# Sheet1.net
KiCad netlist of a schematic drawn in Altium Designer
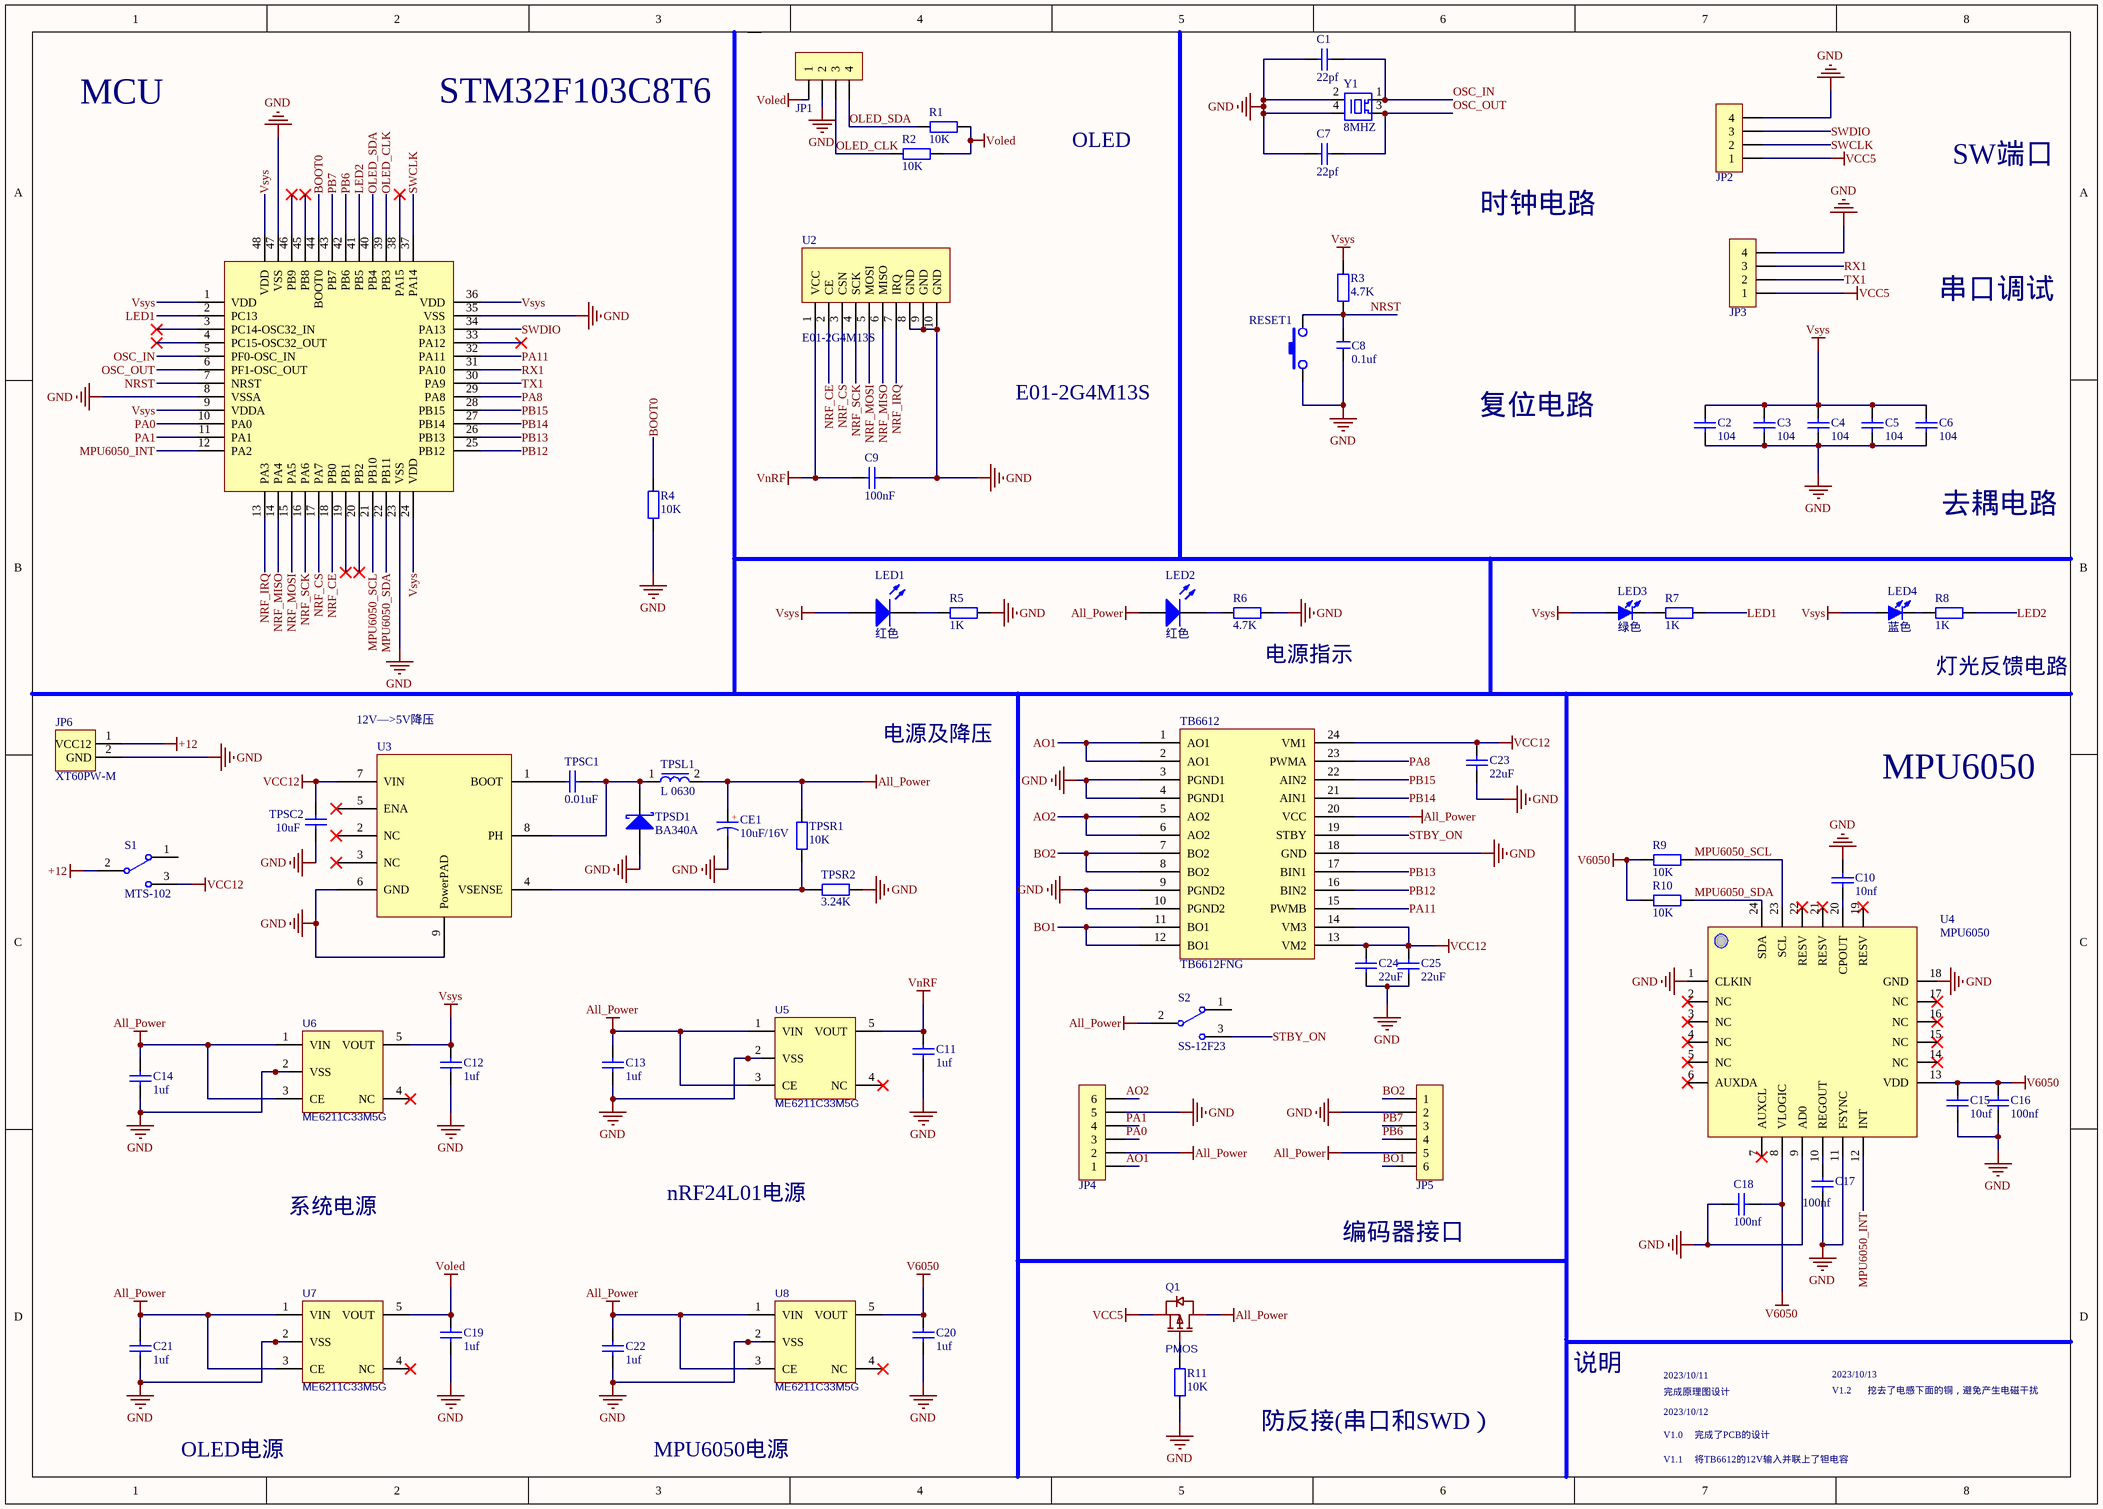
[diagram p0: Sheet1.SchDoc]

(export (version "E")
  (design (tool "Eeschema 10.0.6"))
  (components
    (comp (ref "C1")
      (value "22pf")
      (footprint "C0603_M")
      (description "贴片电容")
      (libsource (lib "cdud开发板") (part "C"))
    )
    (comp (ref "C2")
      (value "104")
      (footprint "C0603_M")
      (description "贴片电容/MLCC电容")
      (libsource (lib "0.1 - 电阻-电容-电感-保险丝-晶振-晶体-磁珠-电位器-法拉电容-馈通电容") (part "C"))
    )
    (comp (ref "C3")
      (value "104")
      (footprint "C0603_M")
      (description "贴片电容/MLCC电容")
      (libsource (lib "0.1 - 电阻-电容-电感-保险丝-晶振-晶体-磁珠-电位器-法拉电容-馈通电容") (part "C"))
    )
    (comp (ref "C4")
      (value "104")
      (footprint "C0603_M")
      (description "贴片电容/MLCC电容")
      (libsource (lib "0.1 - 电阻-电容-电感-保险丝-晶振-晶体-磁珠-电位器-法拉电容-馈通电容") (part "C"))
    )
    (comp (ref "C5")
      (value "104")
      (footprint "C0603_M")
      (description "贴片电容/MLCC电容")
      (libsource (lib "0.1 - 电阻-电容-电感-保险丝-晶振-晶体-磁珠-电位器-法拉电容-馈通电容") (part "C"))
    )
    (comp (ref "C6")
      (value "104")
      (footprint "C0603_M")
      (description "贴片电容/MLCC电容")
      (libsource (lib "0.1 - 电阻-电容-电感-保险丝-晶振-晶体-磁珠-电位器-法拉电容-馈通电容") (part "C"))
    )
    (comp (ref "C7")
      (value "22pf")
      (footprint "C0603_M")
      (description "贴片电容")
      (libsource (lib "cdud开发板") (part "C"))
    )
    (comp (ref "C8")
      (value "0.1uf")
      (footprint "C0603_M")
      (description "无极性贴片电容")
      (fields (field (name "版权归属") "源创客"))
      (libsource (lib "AllSystem") (part "C"))
    )
    (comp (ref "C9")
      (value "100nF")
      (footprint "C0603_M")
      (description "贴片电容")
      (libsource (lib "数传模块") (part "C"))
    )
    (comp (ref "C10")
      (value "10nf")
      (footprint "C0603_M")
      (description "贴片电容")
      (libsource (lib "cdud开发板") (part "C_1"))
    )
    (comp (ref "C11")
      (value "1uf")
      (footprint "C0603_M")
      (description "贴片电容")
      (libsource (lib "cdud开发板") (part "C_3"))
    )
    (comp (ref "C12")
      (value "1uf")
      (footprint "C0603_M")
      (description "贴片电容")
      (libsource (lib "cdud开发板") (part "C_3"))
    )
    (comp (ref "C13")
      (value "1uf")
      (footprint "C0603_M")
      (description "贴片电容")
      (libsource (lib "cdud开发板") (part "C_3"))
    )
    (comp (ref "C14")
      (value "1uf")
      (footprint "C0603_M")
      (description "贴片电容")
      (libsource (lib "cdud开发板") (part "C_3"))
    )
    (comp (ref "C15")
      (value "10uf")
      (footprint "C0603_M")
      (description "贴片电容")
      (libsource (lib "cdud开发板") (part "C_1"))
    )
    (comp (ref "C16")
      (value "100nf")
      (footprint "C0603_M")
      (description "贴片电容")
      (libsource (lib "cdud开发板") (part "C_1"))
    )
    (comp (ref "C17")
      (value "100nf")
      (footprint "C0603_M")
      (description "贴片电容")
      (libsource (lib "cdud开发板") (part "C_1"))
    )
    (comp (ref "C18")
      (value "100nf")
      (footprint "C0603_M")
      (description "贴片电容")
      (libsource (lib "cdud开发板") (part "C_1"))
    )
    (comp (ref "C19")
      (value "1uf")
      (footprint "C0603_M")
      (description "贴片电容")
      (libsource (lib "cdud开发板") (part "C_3"))
    )
    (comp (ref "C20")
      (value "1uf")
      (footprint "C0603_M")
      (description "贴片电容")
      (libsource (lib "cdud开发板") (part "C_3"))
    )
    (comp (ref "C21")
      (value "1uf")
      (footprint "C0603_M")
      (description "贴片电容")
      (libsource (lib "cdud开发板") (part "C_3"))
    )
    (comp (ref "C22")
      (value "1uf")
      (footprint "C0603_M")
      (description "贴片电容")
      (libsource (lib "cdud开发板") (part "C_3"))
    )
    (comp (ref "C23")
      (value "22uF")
      (footprint "C_3216")
      (description "贴片电容/MLCC电容")
      (libsource (lib "0.1 - 电阻-电容-电感-保险丝-晶振-晶体-磁珠-电位器-法拉电容-馈通电容") (part "C"))
    )
    (comp (ref "C24")
      (value "22uF")
      (footprint "C0603_M")
      (description "贴片电容/MLCC电容")
      (libsource (lib "0.1 - 电阻-电容-电感-保险丝-晶振-晶体-磁珠-电位器-法拉电容-馈通电容") (part "C"))
    )
    (comp (ref "C25")
      (value "22uF")
      (footprint "C0603_M")
      (description "贴片电容/MLCC电容")
      (libsource (lib "0.1 - 电阻-电容-电感-保险丝-晶振-晶体-磁珠-电位器-法拉电容-馈通电容") (part "C"))
    )
    (comp (ref "CE1")
      (value "10uF/16V")
      (footprint "CE-3.5*8*11.5 - BK - duplicate")
      (description "直插电解电容")
      (libsource (lib "0.1 - 电阻-电容-电感-晶振-晶体-磁珠-电位器") (part "CE"))
    )
    (comp (ref "JP1")
      (value "HDR-1X4")
      (footprint "HDR2.54-M-LI-4P")
      (description "4P接插件")
      (libsource (lib "5.5 - 2.54mm(100mil)连接器(XH2.54)") (part "Header 4"))
    )
    (comp (ref "JP2")
      (value "HDR-1X4")
      (footprint "HDR2.54-M-LI-4P")
      (description "4P接插件")
      (libsource (lib "") (part "Header 4_1"))
    )
    (comp (ref "JP3")
      (value "HDR-1X4")
      (footprint "HDR2.54-M-LI-4P")
      (description "4P接插件")
      (libsource (lib "") (part "Header 4_1"))
    )
    (comp (ref "JP4")
      (value "HDR-1X6")
      (footprint "XH2.54-LI-6P")
      (description "6P接插件")
      (libsource (lib "5.5 - 2.54mm连接器(KF2EDGK_XH2.54_2.54排针排母)") (part "Header 6"))
    )
    (comp (ref "JP5")
      (value "HDR-1X6")
      (footprint "XH2.54-LI-6P")
      (description "6P接插件")
      (libsource (lib "") (part "Header 6_1"))
    )
    (comp (ref "JP6")
      (value "XT60PW-M")
      (footprint "XT60PW-M")
      (description "XT60PW-M弯插")
      (libsource (lib "XT60PW") (part "XT60PW"))
    )
    (comp (ref "LED1")
      (value "红色")
      (footprint "LED0805_B")
      (description "贴片LED")
      (libsource (lib "0.3 - LED发光二极管-IR二极管_接收管-光耦") (part "LED"))
    )
    (comp (ref "LED2")
      (value "红色")
      (footprint "LED0805_B")
      (description "贴片LED")
      (libsource (lib "0.3 - LED发光二极管-IR二极管_接收管-光耦") (part "LED"))
    )
    (comp (ref "LED3")
      (value "绿色")
      (footprint "LED0805_B")
      (description "贴片LED")
      (libsource (lib "0.3 - LED发光二极管-IR二极管_接收管-光耦") (part "LED-SMD"))
    )
    (comp (ref "LED4")
      (value "蓝色")
      (footprint "LED0805_R")
      (description "贴片LED")
      (libsource (lib "0.3 - LED发光二极管-IR二极管_接收管-光耦") (part "LED-SMD"))
    )
    (comp (ref "MCU")
      (value "STM32F103C8T6")
      (footprint "STM-LQFP48_N")
      (libsource (lib "Schlib1") (part "STM32_LQFP48"))
    )
    (comp (ref "Q1")
      (value "PMOS")
      (footprint "SOT23")
      (fields
        (field (name "BOM_SUPPLIER PART") "C727156")
        (field (name "BOM_MANUFACTURER PART") "AO3401")
        (field (name "CONTRIBUTOR") "LCSC")
      )
      (libsource (lib "IMU") (part "PMOS"))
    )
    (comp (ref "R1")
      (value "10K")
      (footprint "R0603_M")
      (description "贴片电阻")
      (libsource (lib "cdud开发板") (part "R_1"))
    )
    (comp (ref "R2")
      (value "10K")
      (footprint "R0603_M")
      (description "贴片电阻")
      (libsource (lib "cdud开发板") (part "R_1"))
    )
    (comp (ref "R3")
      (value "4.7K")
      (footprint "R0603_M")
      (description "贴片电阻")
      (fields (field (name "版权归属") "源创客"))
      (libsource (lib "AllSystem") (part "R"))
    )
    (comp (ref "R4")
      (value "10K")
      (footprint "R0603_M")
      (description "贴片电阻")
      (libsource (lib "cdud开发板") (part "R"))
    )
    (comp (ref "R5")
      (value "1K")
      (footprint "R0603_M")
      (description "贴片电阻")
      (libsource (lib "0.1 - 电阻-电容-电感-晶振-晶体-磁珠-电位器") (part "R"))
    )
    (comp (ref "R6")
      (value "4.7K")
      (footprint "R0603_M")
      (description "贴片电阻")
      (libsource (lib "cdud开发板") (part "R"))
    )
    (comp (ref "R7")
      (value "1K")
      (footprint "R0603_M")
      (description "贴片电阻")
      (libsource (lib "0.1 - 电阻-电容-电感-晶振-晶体-磁珠-电位器") (part "R"))
    )
    (comp (ref "R8")
      (value "1K")
      (footprint "R0603_M")
      (description "贴片电阻")
      (libsource (lib "0.1 - 电阻-电容-电感-晶振-晶体-磁珠-电位器") (part "R"))
    )
    (comp (ref "R9")
      (value "10K")
      (footprint "R0603_M")
      (description "贴片电阻")
      (libsource (lib "cdud开发板") (part "R"))
    )
    (comp (ref "R10")
      (value "10K")
      (footprint "R0603_M")
      (description "贴片电阻")
      (libsource (lib "cdud开发板") (part "R"))
    )
    (comp (ref "R11")
      (value "10K")
      (footprint "R0603_M")
      (description "贴片电阻")
      (libsource (lib "数传模块") (part "R"))
    )
    (comp (ref "RESET1") (value "KEY") (footprint "SW SMD-3*6*5") (libsource (lib "STM32") (part "KEY")))
    (comp (ref "S1")
      (value "MTS-102")
      (footprint "MTS-10x")
      (description "MTS10x系列3脚扭子开关")
      (fields (field (name "版权归属") "源创客"))
      (libsource (lib "S109Controller") (part "MTS-10x"))
    )
    (comp (ref "S2")
      (value "SS-12F23")
      (footprint "SS-12D0703")
      (description "1路波动开关")
      (fields (field (name "版权归属") "源创客"))
      (libsource (lib "Remote_control") (part "SSW-1P"))
    )
    (comp (ref "TB6612")
      (value "TB6612FNG")
      (footprint "SSOP-24_L8.3-W5.6-P0.65-LS7.6-BL")
      (libsource (lib "Schlib1") (part "TB6612FNG"))
    )
    (comp (ref "TPSC1")
      (value "0.01uF")
      (footprint "C0603_M")
      (description "贴片电容")
      (libsource (lib "0.1 - 电阻-电容-电感-晶振-晶体-磁珠-电位器") (part "C"))
    )
    (comp (ref "TPSC2")
      (value "10uF")
      (footprint "C0603_M")
      (description "贴片电容")
      (libsource (lib "0.1 - 电阻-电容-电感-晶振-晶体-磁珠-电位器") (part "C"))
    )
    (comp (ref "TPSD1")
      (value "BA340A")
      (footprint "SMA")
      (description "肖特基二极管")
      (libsource (lib "0.2 - 二极管-TVS-ESD-整流桥") (part "SS210"))
    )
    (comp (ref "TPSL1")
      (value "L 0630")
      (footprint "L 0630")
      (description "SMA")
      (libsource (lib "mylibrary") (part "L 0630"))
    )
    (comp (ref "TPSR1")
      (value "10K")
      (footprint "R0603_M")
      (description "贴片电阻")
      (libsource (lib "0.1 - 电阻-电容-电感-晶振-晶体-磁珠-电位器") (part "R"))
    )
    (comp (ref "TPSR2")
      (value "3.24K")
      (footprint "R0603_M")
      (description "贴片电阻")
      (libsource (lib "0.1 - 电阻-电容-电感-晶振-晶体-磁珠-电位器") (part "R"))
    )
    (comp (ref "U2")
      (value "E01-2G4M13S")
      (footprint "E01-2G4M01S1B")
      (description "贴片NREF24L01")
      (libsource (lib "IMU") (part "E01-2G4M13S"))
    )
    (comp (ref "U3")
      (value "TPS5430DDAR")
      (footprint "TPS5430DAR")
      (description "输出额定电流3A 纹波30mV")
      (libsource (lib "mylibrary") (part "TPS5430DDAR"))
    )
    (comp (ref "U4")
      (value "MPU6050")
      (footprint "QFN24 4x4_M")
      (description "9轴运动处理传感器")
      (libsource (lib "S109Controller") (part "MPU6050"))
    )
    (comp (ref "U5")
      (value "ME6211C33M5G")
      (footprint "SOT-23-5")
      (description "LDO 3.3V/0.5A")
      (libsource (lib "0.7 - 电源类芯片") (part "ME6211C33"))
    )
    (comp (ref "U6")
      (value "ME6211C33M5G")
      (footprint "SOT-23-5")
      (description "LDO 3.3V/0.5A")
      (libsource (lib "0.7 - 电源类芯片") (part "ME6211C33"))
    )
    (comp (ref "U7")
      (value "ME6211C33M5G")
      (footprint "SOT-23-5")
      (description "LDO 3.3V/0.5A")
      (libsource (lib "0.7 - 电源类芯片") (part "ME6211C33"))
    )
    (comp (ref "U8")
      (value "ME6211C33M5G")
      (footprint "SOT-23-5")
      (description "LDO 3.3V/0.5A")
      (libsource (lib "0.7 - 电源类芯片") (part "ME6211C33"))
    )
    (comp (ref "Y1") (value "8MHZ") (footprint "3225") (libsource (lib "cdud开发板") (part "jinzheng")))
  )
  (nets
    (net (code "1") (name "+12") (class "Default")
      (node (ref "JP6") (pin "1") (pinfunction "VCC12_1") (pintype "passive"))
      (node (ref "S1") (pin "2") (pinfunction "2_2") (pintype "passive"))
    )
    (net (code "2") (name "/AO1") (class "Default")
      (node (ref "JP4") (pin "1") (pinfunction "1_1") (pintype "passive"))
      (node (ref "TB6612") (pin "1") (pinfunction "AO1_1") (pintype "passive"))
      (node (ref "TB6612") (pin "2") (pinfunction "AO1_2") (pintype "passive"))
    )
    (net (code "3") (name "/AO2") (class "Default")
      (node (ref "JP4") (pin "6") (pinfunction "6_6") (pintype "passive"))
      (node (ref "TB6612") (pin "5") (pinfunction "AO2_5") (pintype "passive"))
      (node (ref "TB6612") (pin "6") (pinfunction "AO2_6") (pintype "passive"))
    )
    (net (code "4") (name "/BO1") (class "Default")
      (node (ref "JP5") (pin "6") (pinfunction "6_6") (pintype "passive"))
      (node (ref "TB6612") (pin "11") (pinfunction "BO1_11") (pintype "passive"))
      (node (ref "TB6612") (pin "12") (pinfunction "BO1_12") (pintype "passive"))
    )
    (net (code "5") (name "/BO2") (class "Default")
      (node (ref "JP5") (pin "1") (pinfunction "1_1") (pintype "passive"))
      (node (ref "TB6612") (pin "7") (pinfunction "BO2_7") (pintype "passive"))
      (node (ref "TB6612") (pin "8") (pinfunction "BO2_8") (pintype "passive"))
    )
    (net (code "6") (name "/BOOT0") (class "Default")
      (node (ref "MCU") (pin "44") (pinfunction "BOOT0_44") (pintype "passive"))
      (node (ref "R4") (pin "1") (pinfunction "1_1") (pintype "passive"))
    )
    (net (code "7") (name "/LED1") (class "Default")
      (node (ref "MCU") (pin "2") (pinfunction "PC13_2") (pintype "passive"))
      (node (ref "R7") (pin "2") (pinfunction "2_2") (pintype "passive"))
    )
    (net (code "8") (name "/LED2") (class "Default")
      (node (ref "MCU") (pin "41") (pinfunction "PB5_41") (pintype "passive"))
      (node (ref "R8") (pin "2") (pinfunction "2_2") (pintype "passive"))
    )
    (net (code "9") (name "/MPU6050_INT") (class "Default")
      (node (ref "MCU") (pin "12") (pinfunction "PA2_12") (pintype "passive"))
      (node (ref "U4") (pin "12") (pinfunction "INT_12") (pintype "passive"))
    )
    (net (code "10") (name "/MPU6050_SCL") (class "Default")
      (node (ref "MCU") (pin "21") (pinfunction "PB10_21") (pintype "passive"))
      (node (ref "R9") (pin "2") (pinfunction "2_2") (pintype "passive"))
      (node (ref "U4") (pin "23") (pinfunction "SCL_23") (pintype "passive"))
    )
    (net (code "11") (name "/MPU6050_SDA") (class "Default")
      (node (ref "MCU") (pin "22") (pinfunction "PB11_22") (pintype "passive"))
      (node (ref "R10") (pin "2") (pinfunction "2_2") (pintype "passive"))
      (node (ref "U4") (pin "24") (pinfunction "SDA_24") (pintype "passive"))
    )
    (net (code "12") (name "/NRF_CE") (class "Default")
      (node (ref "MCU") (pin "18") (pinfunction "PB0_18") (pintype "passive"))
      (node (ref "U2") (pin "2") (pinfunction "CE_2") (pintype "passive"))
    )
    (net (code "13") (name "/NRF_CS") (class "Default")
      (node (ref "MCU") (pin "17") (pinfunction "PA7_17") (pintype "passive"))
      (node (ref "U2") (pin "3") (pinfunction "CSN_3") (pintype "passive"))
    )
    (net (code "14") (name "/NRF_IRQ") (class "Default")
      (node (ref "MCU") (pin "13") (pinfunction "PA3_13") (pintype "passive"))
      (node (ref "U2") (pin "7") (pinfunction "IRQ_7") (pintype "passive"))
    )
    (net (code "15") (name "/NRF_MISO") (class "Default")
      (node (ref "MCU") (pin "14") (pinfunction "PA4_14") (pintype "passive"))
      (node (ref "U2") (pin "6") (pinfunction "MISO_6") (pintype "passive"))
    )
    (net (code "16") (name "/NRF_MOSI") (class "Default")
      (node (ref "MCU") (pin "15") (pinfunction "PA5_15") (pintype "passive"))
      (node (ref "U2") (pin "5") (pinfunction "MOSI_5") (pintype "passive"))
    )
    (net (code "17") (name "/NRF_SCK") (class "Default")
      (node (ref "MCU") (pin "16") (pinfunction "PA6_16") (pintype "passive"))
      (node (ref "U2") (pin "4") (pinfunction "SCK_4") (pintype "passive"))
    )
    (net (code "18") (name "/NRST") (class "Default")
      (node (ref "C8") (pin "1") (pinfunction "1_1") (pintype "passive"))
      (node (ref "MCU") (pin "7") (pinfunction "NRST_7") (pintype "passive"))
      (node (ref "R3") (pin "1") (pinfunction "1_1") (pintype "passive"))
      (node (ref "RESET1") (pin "2") (pinfunction "2_2") (pintype "passive"))
    )
    (net (code "19") (name "/OLED_CLK") (class "Default")
      (node (ref "JP1") (pin "3") (pinfunction "3_3") (pintype "passive"))
      (node (ref "MCU") (pin "39") (pinfunction "PB3_39") (pintype "passive"))
      (node (ref "R2") (pin "1") (pinfunction "1_1") (pintype "passive"))
    )
    (net (code "20") (name "/OLED_SDA") (class "Default")
      (node (ref "JP1") (pin "4") (pinfunction "4_4") (pintype "passive"))
      (node (ref "MCU") (pin "40") (pinfunction "PB4_40") (pintype "passive"))
      (node (ref "R1") (pin "1") (pinfunction "1_1") (pintype "passive"))
    )
    (net (code "21") (name "/OSC_IN") (class "Default")
      (node (ref "C1") (pin "2") (pinfunction "2_2") (pintype "passive"))
      (node (ref "MCU") (pin "5") (pinfunction "PF0-OSC_IN_5") (pintype "passive"))
      (node (ref "Y1") (pin "1") (pinfunction "XTAL1_1") (pintype "passive"))
    )
    (net (code "22") (name "/OSC_OUT") (class "Default")
      (node (ref "C7") (pin "2") (pinfunction "2_2") (pintype "passive"))
      (node (ref "MCU") (pin "6") (pinfunction "PF1-OSC_OUT_6") (pintype "passive"))
      (node (ref "Y1") (pin "3") (pinfunction "XTAL3_3") (pintype "passive"))
    )
    (net (code "23") (name "/PA0") (class "Default")
      (node (ref "JP4") (pin "3") (pinfunction "3_3") (pintype "passive"))
      (node (ref "MCU") (pin "10") (pinfunction "PA0_10") (pintype "passive"))
    )
    (net (code "24") (name "/PA1") (class "Default")
      (node (ref "JP4") (pin "4") (pinfunction "4_4") (pintype "passive"))
      (node (ref "MCU") (pin "11") (pinfunction "PA1_11") (pintype "passive"))
    )
    (net (code "25") (name "/PA8") (class "Default")
      (node (ref "MCU") (pin "29") (pinfunction "PA8_29") (pintype "passive"))
      (node (ref "TB6612") (pin "23") (pinfunction "PWMA_23") (pintype "passive"))
    )
    (net (code "26") (name "/PA11") (class "Default")
      (node (ref "MCU") (pin "32") (pinfunction "PA11_32") (pintype "passive"))
      (node (ref "TB6612") (pin "15") (pinfunction "PWMB_15") (pintype "passive"))
    )
    (net (code "27") (name "/PB6") (class "Default")
      (node (ref "JP5") (pin "4") (pinfunction "4_4") (pintype "passive"))
      (node (ref "MCU") (pin "42") (pinfunction "PB6_42") (pintype "passive"))
    )
    (net (code "28") (name "/PB7") (class "Default")
      (node (ref "JP5") (pin "3") (pinfunction "3_3") (pintype "passive"))
      (node (ref "MCU") (pin "43") (pinfunction "PB7_43") (pintype "passive"))
    )
    (net (code "29") (name "/PB12") (class "Default")
      (node (ref "MCU") (pin "25") (pinfunction "PB12_25") (pintype "passive"))
      (node (ref "TB6612") (pin "16") (pinfunction "BIN2_16") (pintype "passive"))
    )
    (net (code "30") (name "/PB13") (class "Default")
      (node (ref "MCU") (pin "26") (pinfunction "PB13_26") (pintype "passive"))
      (node (ref "TB6612") (pin "17") (pinfunction "BIN1_17") (pintype "passive"))
    )
    (net (code "31") (name "/PB14") (class "Default")
      (node (ref "MCU") (pin "27") (pinfunction "PB14_27") (pintype "passive"))
      (node (ref "TB6612") (pin "21") (pinfunction "AIN1_21") (pintype "passive"))
    )
    (net (code "32") (name "/PB15") (class "Default")
      (node (ref "MCU") (pin "28") (pinfunction "PB15_28") (pintype "passive"))
      (node (ref "TB6612") (pin "22") (pinfunction "AIN2_22") (pintype "passive"))
    )
    (net (code "33") (name "/RX1") (class "Default")
      (node (ref "JP3") (pin "3") (pinfunction "3_3") (pintype "passive"))
      (node (ref "MCU") (pin "31") (pinfunction "PA10_31") (pintype "passive"))
    )
    (net (code "34") (name "/STBY_ON") (class "Default")
      (node (ref "S2") (pin "3") (pinfunction "3_3") (pintype "passive"))
      (node (ref "TB6612") (pin "19") (pinfunction "STBY_19") (pintype "passive"))
    )
    (net (code "35") (name "/SWCLK") (class "Default")
      (node (ref "JP2") (pin "2") (pinfunction "2_2") (pintype "passive"))
      (node (ref "MCU") (pin "37") (pinfunction "PA14_37") (pintype "passive"))
    )
    (net (code "36") (name "/SWDIO") (class "Default")
      (node (ref "JP2") (pin "3") (pinfunction "3_3") (pintype "passive"))
      (node (ref "MCU") (pin "34") (pinfunction "PA13_34") (pintype "passive"))
    )
    (net (code "37") (name "/TX1") (class "Default")
      (node (ref "JP3") (pin "2") (pinfunction "2_2") (pintype "passive"))
      (node (ref "MCU") (pin "30") (pinfunction "PA9_30") (pintype "passive"))
    )
    (net (code "38") (name "All_Power") (class "Default")
      (node (ref "C13") (pin "2") (pinfunction "2_2") (pintype "passive"))
      (node (ref "C14") (pin "2") (pinfunction "2_2") (pintype "passive"))
      (node (ref "C21") (pin "2") (pinfunction "2_2") (pintype "passive"))
      (node (ref "C22") (pin "2") (pinfunction "2_2") (pintype "passive"))
      (node (ref "CE1") (pin "1") (pinfunction "1_1") (pintype "passive"))
      (node (ref "JP4") (pin "2") (pinfunction "2_2") (pintype "passive"))
      (node (ref "JP5") (pin "5") (pinfunction "5_5") (pintype "passive"))
      (node (ref "LED2") (pin "1") (pinfunction "A_1") (pintype "passive"))
      (node (ref "Q1") (pin "3") (pinfunction "D_3") (pintype "passive"))
      (node (ref "S2") (pin "2") (pinfunction "2_2") (pintype "passive"))
      (node (ref "TB6612") (pin "20") (pinfunction "VCC_20") (pintype "passive"))
      (node (ref "TPSL1") (pin "2") (pinfunction "2_2") (pintype "passive"))
      (node (ref "TPSR1") (pin "2") (pinfunction "2_2") (pintype "passive"))
      (node (ref "U5") (pin "1") (pinfunction "VIN_1") (pintype "passive"))
      (node (ref "U5") (pin "3") (pinfunction "CE_3") (pintype "passive"))
      (node (ref "U6") (pin "1") (pinfunction "VIN_1") (pintype "passive"))
      (node (ref "U6") (pin "3") (pinfunction "CE_3") (pintype "passive"))
      (node (ref "U7") (pin "1") (pinfunction "VIN_1") (pintype "passive"))
      (node (ref "U7") (pin "3") (pinfunction "CE_3") (pintype "passive"))
      (node (ref "U8") (pin "1") (pinfunction "VIN_1") (pintype "passive"))
      (node (ref "U8") (pin "3") (pinfunction "CE_3") (pintype "passive"))
    )
    (net (code "39") (name "GND") (class "Default")
      (node (ref "C1") (pin "1") (pinfunction "1_1") (pintype "passive"))
      (node (ref "C10") (pin "2") (pinfunction "2_2") (pintype "passive"))
      (node (ref "C11") (pin "1") (pinfunction "1_1") (pintype "passive"))
      (node (ref "C12") (pin "1") (pinfunction "1_1") (pintype "passive"))
      (node (ref "C13") (pin "1") (pinfunction "1_1") (pintype "passive"))
      (node (ref "C14") (pin "1") (pinfunction "1_1") (pintype "passive"))
      (node (ref "C15") (pin "1") (pinfunction "1_1") (pintype "passive"))
      (node (ref "C16") (pin "1") (pinfunction "1_1") (pintype "passive"))
      (node (ref "C17") (pin "1") (pinfunction "1_1") (pintype "passive"))
      (node (ref "C18") (pin "1") (pinfunction "1_1") (pintype "passive"))
      (node (ref "C19") (pin "1") (pinfunction "1_1") (pintype "passive"))
      (node (ref "C2") (pin "1") (pinfunction "1_1") (pintype "passive"))
      (node (ref "C20") (pin "1") (pinfunction "1_1") (pintype "passive"))
      (node (ref "C21") (pin "1") (pinfunction "1_1") (pintype "passive"))
      (node (ref "C22") (pin "1") (pinfunction "1_1") (pintype "passive"))
      (node (ref "C23") (pin "2") (pinfunction "2_2") (pintype "passive"))
      (node (ref "C24") (pin "1") (pinfunction "1_1") (pintype "passive"))
      (node (ref "C25") (pin "1") (pinfunction "1_1") (pintype "passive"))
      (node (ref "C3") (pin "1") (pinfunction "1_1") (pintype "passive"))
      (node (ref "C4") (pin "1") (pinfunction "1_1") (pintype "passive"))
      (node (ref "C5") (pin "1") (pinfunction "1_1") (pintype "passive"))
      (node (ref "C6") (pin "1") (pinfunction "1_1") (pintype "passive"))
      (node (ref "C7") (pin "1") (pinfunction "1_1") (pintype "passive"))
      (node (ref "C8") (pin "2") (pinfunction "2_2") (pintype "passive"))
      (node (ref "C9") (pin "2") (pinfunction "2_2") (pintype "passive"))
      (node (ref "CE1") (pin "2") (pinfunction "2_2") (pintype "passive"))
      (node (ref "JP1") (pin "2") (pinfunction "2_2") (pintype "passive"))
      (node (ref "JP2") (pin "4") (pinfunction "4_4") (pintype "passive"))
      (node (ref "JP3") (pin "4") (pinfunction "4_4") (pintype "passive"))
      (node (ref "JP4") (pin "5") (pinfunction "5_5") (pintype "passive"))
      (node (ref "JP5") (pin "2") (pinfunction "2_2") (pintype "passive"))
      (node (ref "JP6") (pin "2") (pinfunction "GND_2") (pintype "passive"))
      (node (ref "MCU") (pin "23") (pinfunction "VSS_23") (pintype "passive"))
      (node (ref "MCU") (pin "35") (pinfunction "VSS_35") (pintype "passive"))
      (node (ref "MCU") (pin "47") (pinfunction "VSS_47") (pintype "passive"))
      (node (ref "MCU") (pin "8") (pinfunction "VSSA_8") (pintype "passive"))
      (node (ref "R11") (pin "1") (pinfunction "1_1") (pintype "passive"))
      (node (ref "R4") (pin "2") (pinfunction "2_2") (pintype "passive"))
      (node (ref "R5") (pin "2") (pinfunction "2_2") (pintype "passive"))
      (node (ref "R6") (pin "1") (pinfunction "1_1") (pintype "passive"))
      (node (ref "RESET1") (pin "1") (pinfunction "1_1") (pintype "passive"))
      (node (ref "TB6612") (pin "10") (pinfunction "PGND2_10") (pintype "passive"))
      (node (ref "TB6612") (pin "18") (pinfunction "GND_18") (pintype "passive"))
      (node (ref "TB6612") (pin "3") (pinfunction "PGND1_3") (pintype "passive"))
      (node (ref "TB6612") (pin "4") (pinfunction "PGND1_4") (pintype "passive"))
      (node (ref "TB6612") (pin "9") (pinfunction "PGND2_9") (pintype "passive"))
      (node (ref "TPSC2") (pin "1") (pinfunction "1_1") (pintype "passive"))
      (node (ref "TPSD1") (pin "1") (pinfunction "A_1") (pintype "passive"))
      (node (ref "TPSR2") (pin "1") (pinfunction "1_1") (pintype "passive"))
      (node (ref "U2") (pin "10") (pinfunction "GND_10") (pintype "passive"))
      (node (ref "U2") (pin "8") (pinfunction "GND_8") (pintype "passive"))
      (node (ref "U2") (pin "9") (pinfunction "GND_9") (pintype "passive"))
      (node (ref "U3") (pin "6") (pinfunction "GND_6") (pintype "passive"))
      (node (ref "U3") (pin "9") (pinfunction "PowerPAD_9") (pintype "passive"))
      (node (ref "U4") (pin "1") (pinfunction "CLKIN_1") (pintype "passive"))
      (node (ref "U4") (pin "11") (pinfunction "FSYNC_11") (pintype "passive"))
      (node (ref "U4") (pin "18") (pinfunction "GND_18") (pintype "passive"))
      (node (ref "U4") (pin "9") (pinfunction "AD0_9") (pintype "passive"))
      (node (ref "U5") (pin "2") (pinfunction "VSS_2") (pintype "passive"))
      (node (ref "U6") (pin "2") (pinfunction "VSS_2") (pintype "passive"))
      (node (ref "U7") (pin "2") (pinfunction "VSS_2") (pintype "passive"))
      (node (ref "U8") (pin "2") (pinfunction "VSS_2") (pintype "passive"))
      (node (ref "Y1") (pin "2") (pinfunction "GND_2") (pintype "passive"))
      (node (ref "Y1") (pin "4") (pinfunction "GND_4") (pintype "passive"))
    )
    (net (code "40") (name "Net-(LED1-K)") (class "Default")
      (node (ref "LED1") (pin "2") (pinfunction "K_2") (pintype "passive"))
      (node (ref "R5") (pin "1") (pinfunction "1_1") (pintype "passive"))
    )
    (net (code "41") (name "Net-(LED2-K)") (class "Default")
      (node (ref "LED2") (pin "2") (pinfunction "K_2") (pintype "passive"))
      (node (ref "R6") (pin "2") (pinfunction "2_2") (pintype "passive"))
    )
    (net (code "42") (name "Net-(LED3-K)") (class "Default")
      (node (ref "LED3") (pin "2") (pinfunction "K_2") (pintype "passive"))
      (node (ref "R7") (pin "1") (pinfunction "1_1") (pintype "passive"))
    )
    (net (code "43") (name "Net-(LED4-K)") (class "Default")
      (node (ref "LED4") (pin "2") (pinfunction "K_2") (pintype "passive"))
      (node (ref "R8") (pin "1") (pinfunction "1_1") (pintype "passive"))
    )
    (net (code "44") (name "Net-(Q1-G)") (class "Default")
      (node (ref "Q1") (pin "1") (pinfunction "G_1") (pintype "passive"))
      (node (ref "R11") (pin "2") (pinfunction "2_2") (pintype "passive"))
    )
    (net (code "45") (name "Net-(TPSD1-K)") (class "Default")
      (node (ref "TPSC1") (pin "1") (pinfunction "1_1") (pintype "passive"))
      (node (ref "TPSD1") (pin "2") (pinfunction "K_2") (pintype "passive"))
      (node (ref "TPSL1") (pin "1") (pinfunction "1_1") (pintype "passive"))
      (node (ref "U3") (pin "8") (pinfunction "PH_8") (pintype "passive"))
    )
    (net (code "46") (name "Net-(U3-BOOT)") (class "Default")
      (node (ref "TPSC1") (pin "2") (pinfunction "2_2") (pintype "passive"))
      (node (ref "U3") (pin "1") (pinfunction "BOOT_1") (pintype "passive"))
    )
    (net (code "47") (name "Net-(U3-VSENSE)") (class "Default")
      (node (ref "TPSR1") (pin "1") (pinfunction "1_1") (pintype "passive"))
      (node (ref "TPSR2") (pin "2") (pinfunction "2_2") (pintype "passive"))
      (node (ref "U3") (pin "4") (pinfunction "VSENSE_4") (pintype "passive"))
    )
    (net (code "48") (name "Net-(U4-CPOUT)") (class "Default")
      (node (ref "C10") (pin "1") (pinfunction "1_1") (pintype "passive"))
      (node (ref "U4") (pin "20") (pinfunction "CPOUT_20") (pintype "passive"))
    )
    (net (code "49") (name "Net-(U4-REGOUT)") (class "Default")
      (node (ref "C17") (pin "2") (pinfunction "2_2") (pintype "passive"))
      (node (ref "U4") (pin "10") (pinfunction "REGOUT_10") (pintype "passive"))
    )
    (net (code "50") (name "V6050") (class "Default")
      (node (ref "C15") (pin "2") (pinfunction "2_2") (pintype "passive"))
      (node (ref "C16") (pin "2") (pinfunction "2_2") (pintype "passive"))
      (node (ref "C18") (pin "2") (pinfunction "2_2") (pintype "passive"))
      (node (ref "C20") (pin "2") (pinfunction "2_2") (pintype "passive"))
      (node (ref "R10") (pin "1") (pinfunction "1_1") (pintype "passive"))
      (node (ref "R9") (pin "1") (pinfunction "1_1") (pintype "passive"))
      (node (ref "U4") (pin "13") (pinfunction "VDD_13") (pintype "passive"))
      (node (ref "U4") (pin "8") (pinfunction "VLOGIC_8") (pintype "passive"))
      (node (ref "U8") (pin "5") (pinfunction "VOUT_5") (pintype "passive"))
    )
    (net (code "51") (name "VCC5") (class "Default")
      (node (ref "JP2") (pin "1") (pinfunction "1_1") (pintype "passive"))
      (node (ref "JP3") (pin "1") (pinfunction "1_1") (pintype "passive"))
      (node (ref "Q1") (pin "2") (pinfunction "S_2") (pintype "passive"))
    )
    (net (code "52") (name "VCC12") (class "Default")
      (node (ref "C23") (pin "1") (pinfunction "1_1") (pintype "passive"))
      (node (ref "C24") (pin "2") (pinfunction "2_2") (pintype "passive"))
      (node (ref "C25") (pin "2") (pinfunction "2_2") (pintype "passive"))
      (node (ref "S1") (pin "3") (pinfunction "3_3") (pintype "passive"))
      (node (ref "TB6612") (pin "13") (pinfunction "VM2_13") (pintype "passive"))
      (node (ref "TB6612") (pin "14") (pinfunction "VM3_14") (pintype "passive"))
      (node (ref "TB6612") (pin "24") (pinfunction "VM1_24") (pintype "passive"))
      (node (ref "TPSC2") (pin "2") (pinfunction "2_2") (pintype "passive"))
      (node (ref "U3") (pin "7") (pinfunction "VIN_7") (pintype "passive"))
    )
    (net (code "53") (name "VnRF") (class "Default")
      (node (ref "C11") (pin "2") (pinfunction "2_2") (pintype "passive"))
      (node (ref "C9") (pin "1") (pinfunction "1_1") (pintype "passive"))
      (node (ref "U2") (pin "1") (pinfunction "VCC_1") (pintype "passive"))
      (node (ref "U5") (pin "5") (pinfunction "VOUT_5") (pintype "passive"))
    )
    (net (code "54") (name "Voled") (class "Default")
      (node (ref "C19") (pin "2") (pinfunction "2_2") (pintype "passive"))
      (node (ref "JP1") (pin "1") (pinfunction "1_1") (pintype "passive"))
      (node (ref "R1") (pin "2") (pinfunction "2_2") (pintype "passive"))
      (node (ref "R2") (pin "2") (pinfunction "2_2") (pintype "passive"))
      (node (ref "U7") (pin "5") (pinfunction "VOUT_5") (pintype "passive"))
    )
    (net (code "55") (name "Vsys") (class "Default")
      (node (ref "C12") (pin "2") (pinfunction "2_2") (pintype "passive"))
      (node (ref "C2") (pin "2") (pinfunction "2_2") (pintype "passive"))
      (node (ref "C3") (pin "2") (pinfunction "2_2") (pintype "passive"))
      (node (ref "C4") (pin "2") (pinfunction "2_2") (pintype "passive"))
      (node (ref "C5") (pin "2") (pinfunction "2_2") (pintype "passive"))
      (node (ref "C6") (pin "2") (pinfunction "2_2") (pintype "passive"))
      (node (ref "LED1") (pin "1") (pinfunction "A_1") (pintype "passive"))
      (node (ref "LED3") (pin "1") (pinfunction "A_1") (pintype "passive"))
      (node (ref "LED4") (pin "1") (pinfunction "A_1") (pintype "passive"))
      (node (ref "MCU") (pin "1") (pinfunction "VDD_1") (pintype "passive"))
      (node (ref "MCU") (pin "24") (pinfunction "VDD_24") (pintype "passive"))
      (node (ref "MCU") (pin "36") (pinfunction "VDD_36") (pintype "passive"))
      (node (ref "MCU") (pin "48") (pinfunction "VDD_48") (pintype "passive"))
      (node (ref "MCU") (pin "9") (pinfunction "VDDA_9") (pintype "passive"))
      (node (ref "R3") (pin "2") (pinfunction "2_2") (pintype "passive"))
      (node (ref "U6") (pin "5") (pinfunction "VOUT_5") (pintype "passive"))
    )
    (net (code "56") (name "unconnected-(MCU-PA12-Pad33)") (class "Default")
      (node (ref "MCU") (pin "33") (pinfunction "PA12_33") (pintype "passive+no_connect"))
    )
    (net (code "57") (name "unconnected-(MCU-PA15-Pad38)") (class "Default")
      (node (ref "MCU") (pin "38") (pinfunction "PA15_38") (pintype "passive+no_connect"))
    )
    (net (code "58") (name "unconnected-(MCU-PB1-Pad19)") (class "Default")
      (node (ref "MCU") (pin "19") (pinfunction "PB1_19") (pintype "passive+no_connect"))
    )
    (net (code "59") (name "unconnected-(MCU-PB2-Pad20)") (class "Default")
      (node (ref "MCU") (pin "20") (pinfunction "PB2_20") (pintype "passive+no_connect"))
    )
    (net (code "60") (name "unconnected-(MCU-PB8-Pad45)") (class "Default")
      (node (ref "MCU") (pin "45") (pinfunction "PB8_45") (pintype "passive+no_connect"))
    )
    (net (code "61") (name "unconnected-(MCU-PB9-Pad46)") (class "Default")
      (node (ref "MCU") (pin "46") (pinfunction "PB9_46") (pintype "passive+no_connect"))
    )
    (net (code "62") (name "unconnected-(MCU-PC14-OSC32_IN-Pad3)") (class "Default")
      (node (ref "MCU") (pin "3") (pinfunction "PC14-OSC32_IN_3") (pintype "passive+no_connect"))
    )
    (net (code "63") (name "unconnected-(MCU-PC15-OSC32_OUT-Pad4)") (class "Default")
      (node (ref "MCU") (pin "4") (pinfunction "PC15-OSC32_OUT_4") (pintype "passive+no_connect"))
    )
    (net (code "64") (name "unconnected-(S1-Pad1)") (class "Default")
      (node (ref "S1") (pin "1") (pinfunction "1_1") (pintype "passive"))
    )
    (net (code "65") (name "unconnected-(S2-Pad1)") (class "Default")
      (node (ref "S2") (pin "1") (pinfunction "1_1") (pintype "passive"))
    )
    (net (code "66") (name "unconnected-(U3-ENA-Pad5)") (class "Default")
      (node (ref "U3") (pin "5") (pinfunction "ENA_5") (pintype "passive+no_connect"))
    )
    (net (code "67") (name "unconnected-(U3-NC-Pad2)") (class "Default")
      (node (ref "U3") (pin "2") (pinfunction "NC_2") (pintype "passive+no_connect"))
    )
    (net (code "68") (name "unconnected-(U3-NC-Pad3)") (class "Default")
      (node (ref "U3") (pin "3") (pinfunction "NC_3") (pintype "passive+no_connect"))
    )
    (net (code "69") (name "unconnected-(U4-AUXCL-Pad7)") (class "Default")
      (node (ref "U4") (pin "7") (pinfunction "AUXCL_7") (pintype "passive+no_connect"))
    )
    (net (code "70") (name "unconnected-(U4-AUXDA-Pad6)") (class "Default")
      (node (ref "U4") (pin "6") (pinfunction "AUXDA_6") (pintype "passive+no_connect"))
    )
    (net (code "71") (name "unconnected-(U4-NC-Pad2)") (class "Default")
      (node (ref "U4") (pin "2") (pinfunction "NC_2") (pintype "passive+no_connect"))
    )
    (net (code "72") (name "unconnected-(U4-NC-Pad3)") (class "Default")
      (node (ref "U4") (pin "3") (pinfunction "NC_3") (pintype "passive+no_connect"))
    )
    (net (code "73") (name "unconnected-(U4-NC-Pad4)") (class "Default")
      (node (ref "U4") (pin "4") (pinfunction "NC_4") (pintype "passive+no_connect"))
    )
    (net (code "74") (name "unconnected-(U4-NC-Pad5)") (class "Default")
      (node (ref "U4") (pin "5") (pinfunction "NC_5") (pintype "passive+no_connect"))
    )
    (net (code "75") (name "unconnected-(U4-NC-Pad14)") (class "Default")
      (node (ref "U4") (pin "14") (pinfunction "NC_14") (pintype "passive+no_connect"))
    )
    (net (code "76") (name "unconnected-(U4-NC-Pad15)") (class "Default")
      (node (ref "U4") (pin "15") (pinfunction "NC_15") (pintype "passive+no_connect"))
    )
    (net (code "77") (name "unconnected-(U4-NC-Pad16)") (class "Default")
      (node (ref "U4") (pin "16") (pinfunction "NC_16") (pintype "passive+no_connect"))
    )
    (net (code "78") (name "unconnected-(U4-NC-Pad17)") (class "Default")
      (node (ref "U4") (pin "17") (pinfunction "NC_17") (pintype "passive+no_connect"))
    )
    (net (code "79") (name "unconnected-(U4-RESV-Pad19)") (class "Default")
      (node (ref "U4") (pin "19") (pinfunction "RESV_19") (pintype "passive+no_connect"))
    )
    (net (code "80") (name "unconnected-(U4-RESV-Pad21)") (class "Default")
      (node (ref "U4") (pin "21") (pinfunction "RESV_21") (pintype "passive+no_connect"))
    )
    (net (code "81") (name "unconnected-(U4-RESV-Pad22)") (class "Default")
      (node (ref "U4") (pin "22") (pinfunction "RESV_22") (pintype "passive+no_connect"))
    )
    (net (code "82") (name "unconnected-(U5-NC-Pad4)") (class "Default")
      (node (ref "U5") (pin "4") (pinfunction "NC_4") (pintype "passive+no_connect"))
    )
    (net (code "83") (name "unconnected-(U6-NC-Pad4)") (class "Default")
      (node (ref "U6") (pin "4") (pinfunction "NC_4") (pintype "passive+no_connect"))
    )
    (net (code "84") (name "unconnected-(U7-NC-Pad4)") (class "Default")
      (node (ref "U7") (pin "4") (pinfunction "NC_4") (pintype "passive+no_connect"))
    )
    (net (code "85") (name "unconnected-(U8-NC-Pad4)") (class "Default")
      (node (ref "U8") (pin "4") (pinfunction "NC_4") (pintype "passive+no_connect"))
    )
  )
)
